# Sheet2.net
KiCad netlist of a schematic drawn in Altium Designer
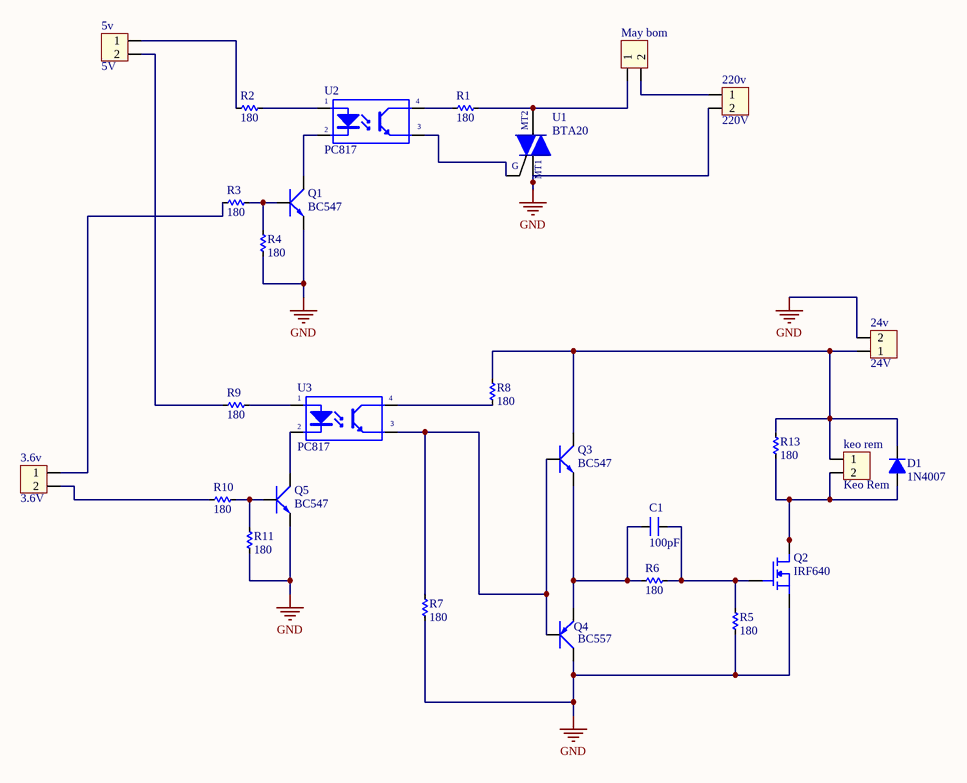
[diagram p0: Sheet2.SchDoc]

(export (version "E")
  (design (tool "Eeschema 10.0.6"))
  (components
    (comp (ref "3.6v")
      (value "3.6V")
      (footprint "HED2")
      (description "Header 2 (Green)")
      (libsource (lib "syhaunguyen__1") (part "Hed2"))
    )
    (comp (ref "5v")
      (value "5V")
      (footprint "HED2")
      (description "Header 2 (Green)")
      (libsource (lib "syhaunguyen__1") (part "Hed2"))
    )
    (comp (ref "24v")
      (value "24V")
      (footprint "HED2")
      (description "Header 2 (Green)")
      (libsource (lib "") (part "Hed2_1"))
    )
    (comp (ref "220v")
      (value "220V")
      (footprint "HED2")
      (description "Header 2 (Green)")
      (libsource (lib "") (part "Hed2_2"))
    )
    (comp (ref "C1")
      (value "100pF")
      (footprint "CN1")
      (description "Cap np  1pF - 472pF")
      (libsource (lib "minhha") (part "CN1"))
    )
    (comp (ref "D1")
      (value "1N4007")
      (footprint "D1A")
      (description "Diode 1A")
      (libsource (lib "minhha") (part "D1A"))
    )
    (comp (ref "keo rem")
      (value "Keo Rem")
      (footprint "HED2")
      (description "Header 2 (Green)")
      (libsource (lib "") (part "Hed2_2"))
    )
    (comp (ref "May bom")
      (value "~")
      (footprint "HED2")
      (description "Header 2 (Green)")
      (libsource (lib "") (part "Hed2_1"))
    )
    (comp (ref "Q1")
      (value "BC547")
      (footprint "QTO-92")
      (description "P 600mW, EBC")
      (libsource (lib "minhha") (part "NPN_EBC"))
    )
    (comp (ref "Q2") (value "IRF640") (footprint "TO220AB") (libsource (lib "minhha") (part "IRF640")))
    (comp (ref "Q3")
      (value "BC547")
      (footprint "QTO-92")
      (description "P 600mW, EBC")
      (libsource (lib "minhha") (part "NPN_EBC"))
    )
    (comp (ref "Q4")
      (value "BC557")
      (footprint "QTO-92")
      (description "P 600mW, EBC")
      (libsource (lib "minhha") (part "PNP_EBC"))
    )
    (comp (ref "Q5")
      (value "BC547")
      (footprint "QTO-92")
      (description "P 600mW, EBC")
      (libsource (lib "minhha") (part "NPN_EBC"))
    )
    (comp (ref "R1")
      (value "180")
      (footprint "RES-1/2W")
      (description "Res")
      (fields
        (field (name "MANUFACTURER") "Generic Components")
        (field (name "PUBLISHER") "Altium Hobart Technology Centre")
      )
      (libsource (lib "Library1") (part "Res"))
    )
    (comp (ref "R2")
      (value "180")
      (footprint "RES-1/2W")
      (description "Res")
      (fields
        (field (name "MANUFACTURER") "Generic Components")
        (field (name "PUBLISHER") "Altium Hobart Technology Centre")
      )
      (libsource (lib "Library1") (part "Res"))
    )
    (comp (ref "R3")
      (value "180")
      (footprint "RES-1/2W")
      (description "Res")
      (fields
        (field (name "MANUFACTURER") "Generic Components")
        (field (name "PUBLISHER") "Altium Hobart Technology Centre")
      )
      (libsource (lib "Library1") (part "Res"))
    )
    (comp (ref "R4")
      (value "180")
      (footprint "RES-1/2W")
      (description "Res")
      (fields
        (field (name "MANUFACTURER") "Generic Components")
        (field (name "PUBLISHER") "Altium Hobart Technology Centre")
      )
      (libsource (lib "Library1") (part "Res"))
    )
    (comp (ref "R5")
      (value "180")
      (footprint "RES-1/2W")
      (description "Res")
      (fields
        (field (name "MANUFACTURER") "Generic Components")
        (field (name "PUBLISHER") "Altium Hobart Technology Centre")
      )
      (libsource (lib "Library1") (part "Res"))
    )
    (comp (ref "R6")
      (value "180")
      (footprint "RES-1/2W")
      (description "Res")
      (fields
        (field (name "MANUFACTURER") "Generic Components")
        (field (name "PUBLISHER") "Altium Hobart Technology Centre")
      )
      (libsource (lib "Library1") (part "Res"))
    )
    (comp (ref "R7")
      (value "180")
      (footprint "RES-1/2W")
      (description "Res")
      (fields
        (field (name "MANUFACTURER") "Generic Components")
        (field (name "PUBLISHER") "Altium Hobart Technology Centre")
      )
      (libsource (lib "Library1") (part "Res"))
    )
    (comp (ref "R8")
      (value "180")
      (footprint "RES-1/2W")
      (description "Res")
      (fields
        (field (name "MANUFACTURER") "Generic Components")
        (field (name "PUBLISHER") "Altium Hobart Technology Centre")
      )
      (libsource (lib "Library1") (part "Res"))
    )
    (comp (ref "R9")
      (value "180")
      (footprint "RES-1/2W")
      (description "Res")
      (fields
        (field (name "MANUFACTURER") "Generic Components")
        (field (name "PUBLISHER") "Altium Hobart Technology Centre")
      )
      (libsource (lib "Library1") (part "Res"))
    )
    (comp (ref "R10")
      (value "180")
      (footprint "RES-1/2W")
      (description "Res")
      (fields
        (field (name "MANUFACTURER") "Generic Components")
        (field (name "PUBLISHER") "Altium Hobart Technology Centre")
      )
      (libsource (lib "Library1") (part "Res"))
    )
    (comp (ref "R11")
      (value "180")
      (footprint "RES-1/2W")
      (description "Res")
      (fields
        (field (name "MANUFACTURER") "Generic Components")
        (field (name "PUBLISHER") "Altium Hobart Technology Centre")
      )
      (libsource (lib "Library1") (part "Res"))
    )
    (comp (ref "R13")
      (value "180")
      (footprint "RES-1/2W")
      (description "Res")
      (fields
        (field (name "MANUFACTURER") "Generic Components")
        (field (name "PUBLISHER") "Altium Hobart Technology Centre")
      )
      (libsource (lib "Library1") (part "Res"))
    )
    (comp (ref "U1")
      (value "BTA20")
      (footprint "TO-220MAX")
      (description "Triacs - 20A")
      (libsource (lib "Compiled_Devzone") (part "BTA20"))
    )
    (comp (ref "U2")
      (value "PC817")
      (footprint "DIP4")
      (description "Single Opto")
      (libsource (lib "Library1") (part "PC817"))
    )
    (comp (ref "U3")
      (value "PC817")
      (footprint "DIP4")
      (description "Single Opto")
      (libsource (lib "Library1") (part "PC817"))
    )
  )
  (nets
    (net (code "1") (name "GND") (class "Default")
      (node (ref "220v") (pin "2") (pinfunction "2_2") (pintype "passive"))
      (node (ref "24v") (pin "2") (pinfunction "2_2") (pintype "passive"))
      (node (ref "Q1") (pin "1") (pinfunction "E_1") (pintype "passive"))
      (node (ref "Q2") (pin "3") (pinfunction "S_3") (pintype "passive"))
      (node (ref "Q4") (pin "3") (pinfunction "C_3") (pintype "passive"))
      (node (ref "Q5") (pin "1") (pinfunction "E_1") (pintype "passive"))
      (node (ref "R11") (pin "1") (pinfunction "1_1") (pintype "passive"))
      (node (ref "R4") (pin "1") (pinfunction "1_1") (pintype "passive"))
      (node (ref "R5") (pin "1") (pinfunction "1_1") (pintype "passive"))
      (node (ref "R7") (pin "1") (pinfunction "1_1") (pintype "passive"))
      (node (ref "U1") (pin "1") (pinfunction "MT1_1") (pintype "passive"))
    )
    (net (code "2") (name "Net-(3.6v-Pad1)") (class "Default")
      (node (ref "3.6v") (pin "1") (pinfunction "1_1") (pintype "passive"))
      (node (ref "R3") (pin "1") (pinfunction "1_1") (pintype "passive"))
    )
    (net (code "3") (name "Net-(3.6v-Pad2)") (class "Default")
      (node (ref "3.6v") (pin "2") (pinfunction "2_2") (pintype "passive"))
      (node (ref "R10") (pin "1") (pinfunction "1_1") (pintype "passive"))
    )
    (net (code "4") (name "Net-(5v-Pad1)") (class "Default")
      (node (ref "5v") (pin "1") (pinfunction "1_1") (pintype "passive"))
      (node (ref "R2") (pin "1") (pinfunction "1_1") (pintype "passive"))
    )
    (net (code "5") (name "Net-(5v-Pad2)") (class "Default")
      (node (ref "5v") (pin "2") (pinfunction "2_2") (pintype "passive"))
      (node (ref "R9") (pin "1") (pinfunction "1_1") (pintype "passive"))
    )
    (net (code "6") (name "Net-(220v-Pad1)") (class "Default")
      (node (ref "220v") (pin "1") (pinfunction "1_1") (pintype "passive"))
      (node (ref "May bom") (pin "2") (pinfunction "2_2") (pintype "passive"))
    )
    (net (code "7") (name "Net-(D1-A)") (class "Default")
      (node (ref "D1") (pin "1") (pinfunction "A_1") (pintype "passive"))
      (node (ref "Q2") (pin "2") (pinfunction "D_2") (pintype "passive"))
      (node (ref "R13") (pin "1") (pinfunction "1_1") (pintype "passive"))
      (node (ref "keo rem") (pin "2") (pinfunction "2_2") (pintype "passive"))
    )
    (net (code "8") (name "Net-(D1-K)") (class "Default")
      (node (ref "24v") (pin "1") (pinfunction "1_1") (pintype "passive"))
      (node (ref "D1") (pin "2") (pinfunction "K_2") (pintype "passive"))
      (node (ref "Q3") (pin "3") (pinfunction "C_3") (pintype "passive"))
      (node (ref "R13") (pin "2") (pinfunction "2_2") (pintype "passive"))
      (node (ref "R8") (pin "2") (pinfunction "2_2") (pintype "passive"))
      (node (ref "keo rem") (pin "1") (pinfunction "1_1") (pintype "passive"))
    )
    (net (code "9") (name "Net-(Q1-B)") (class "Default")
      (node (ref "Q1") (pin "2") (pinfunction "B_2") (pintype "passive"))
      (node (ref "R3") (pin "2") (pinfunction "2_2") (pintype "passive"))
      (node (ref "R4") (pin "2") (pinfunction "2_2") (pintype "passive"))
    )
    (net (code "10") (name "Net-(Q1-C)") (class "Default")
      (node (ref "Q1") (pin "3") (pinfunction "C_3") (pintype "passive"))
      (node (ref "U2") (pin "2") (pinfunction "K_2") (pintype "passive"))
    )
    (net (code "11") (name "Net-(Q2-G)") (class "Default")
      (node (ref "C1") (pin "2") (pinfunction "2_2") (pintype "passive"))
      (node (ref "Q2") (pin "1") (pinfunction "G_1") (pintype "passive"))
      (node (ref "R5") (pin "2") (pinfunction "2_2") (pintype "passive"))
      (node (ref "R6") (pin "2") (pinfunction "2_2") (pintype "passive"))
    )
    (net (code "12") (name "Net-(Q3-B)") (class "Default")
      (node (ref "Q3") (pin "2") (pinfunction "B_2") (pintype "passive"))
      (node (ref "Q4") (pin "2") (pinfunction "B_2") (pintype "passive"))
      (node (ref "R7") (pin "2") (pinfunction "2_2") (pintype "passive"))
      (node (ref "U3") (pin "3") (pinfunction "E_3") (pintype "passive"))
    )
    (net (code "13") (name "Net-(Q3-E)") (class "Default")
      (node (ref "C1") (pin "1") (pinfunction "1_1") (pintype "passive"))
      (node (ref "Q3") (pin "1") (pinfunction "E_1") (pintype "passive"))
      (node (ref "Q4") (pin "1") (pinfunction "E_1") (pintype "passive"))
      (node (ref "R6") (pin "1") (pinfunction "1_1") (pintype "passive"))
    )
    (net (code "14") (name "Net-(Q5-B)") (class "Default")
      (node (ref "Q5") (pin "2") (pinfunction "B_2") (pintype "passive"))
      (node (ref "R10") (pin "2") (pinfunction "2_2") (pintype "passive"))
      (node (ref "R11") (pin "2") (pinfunction "2_2") (pintype "passive"))
    )
    (net (code "15") (name "Net-(Q5-C)") (class "Default")
      (node (ref "Q5") (pin "3") (pinfunction "C_3") (pintype "passive"))
      (node (ref "U3") (pin "2") (pinfunction "K_2") (pintype "passive"))
    )
    (net (code "16") (name "Net-(U1-IN)") (class "Default")
      (node (ref "U1") (pin "3") (pinfunction "IN_3") (pintype "passive"))
      (node (ref "U2") (pin "3") (pinfunction "E_3") (pintype "passive"))
    )
    (net (code "17") (name "Net-(U1-MT2)") (class "Default")
      (node (ref "May bom") (pin "1") (pinfunction "1_1") (pintype "passive"))
      (node (ref "R1") (pin "2") (pinfunction "2_2") (pintype "passive"))
      (node (ref "U1") (pin "2") (pinfunction "MT2_2") (pintype "passive"))
    )
    (net (code "18") (name "Net-(U2-A)") (class "Default")
      (node (ref "R2") (pin "2") (pinfunction "2_2") (pintype "passive"))
      (node (ref "U2") (pin "1") (pinfunction "A_1") (pintype "passive"))
    )
    (net (code "19") (name "Net-(U2-C)") (class "Default")
      (node (ref "R1") (pin "1") (pinfunction "1_1") (pintype "passive"))
      (node (ref "U2") (pin "4") (pinfunction "C_4") (pintype "passive"))
    )
    (net (code "20") (name "Net-(U3-A)") (class "Default")
      (node (ref "R9") (pin "2") (pinfunction "2_2") (pintype "passive"))
      (node (ref "U3") (pin "1") (pinfunction "A_1") (pintype "passive"))
    )
    (net (code "21") (name "Net-(U3-C)") (class "Default")
      (node (ref "R8") (pin "1") (pinfunction "1_1") (pintype "passive"))
      (node (ref "U3") (pin "4") (pinfunction "C_4") (pintype "passive"))
    )
  )
)
